# SurfacePressureSensor_V1.net
KiCad netlist of a schematic drawn in Altium Designer
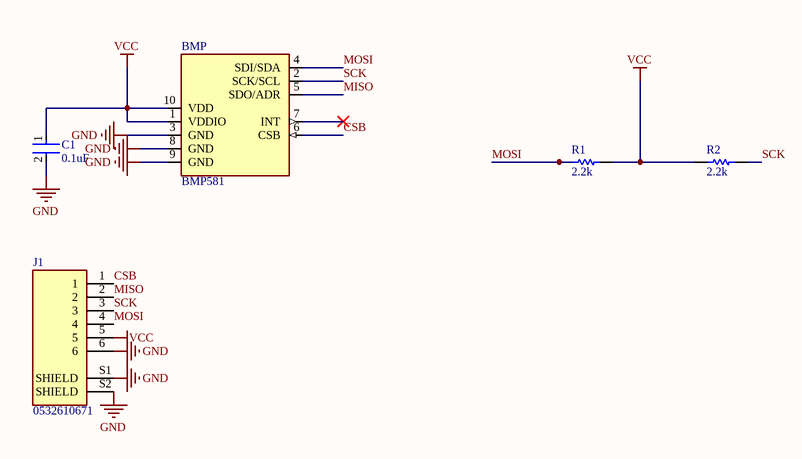
[diagram p0: SurfacePressureSensor_V1.SchDoc]

(export (version "E")
  (design (tool "Eeschema 10.0.6"))
  (components
    (comp (ref "BMP")
      (value "BMP581")
      (footprint "BMP581")
      (fields (field (name "MF") "Bosch"))
      (libsource (lib "BMP581") (part "BMP581"))
    )
    (comp (ref "C1")
      (value "0.1uF")
      (footprint "FP-C0805C-DG-MFG")
      (description "CAP CER 10UF 10V X5R 0805")
      (fields (field (name "TOLERANCE") "10%") (field (name "MANUFACTURER PART NUMBER") "C0805C106K8PACTU"))
      (libsource (lib "Altium Content Vault") (part "11868f565c42a9108669ba33697ecf6"))
    )
    (comp (ref "J1")
      (value "0532610671")
      (footprint "MOLEX_0532610671")
      (description "Picoblade Connector, 6 Circuit Single Row, Right Angle Surface Mount SMT PCB")
      (fields (field (name "DIGI-KEY_PART_NUMBER") "WM7624CT-ND") (field (name "MF") "Molex"))
      (libsource (lib "0532610671") (part "0532610671"))
    )
    (comp (ref "R1")
      (value "2.2k")
      (footprint "RESC2013X50X30LL20T20")
      (fields (field (name "MANUFACTURER") "Vishay Dale") (field (name "PART NUMBER") "CRCW08050000Z0EA"))
      (libsource (lib "Altium Content Vault") (part "RES"))
    )
    (comp (ref "R2")
      (value "2.2k")
      (footprint "RESC2013X50X30LL20T20")
      (fields (field (name "MANUFACTURER") "Vishay Dale") (field (name "PART NUMBER") "CRCW08050000Z0EA"))
      (libsource (lib "Altium Content Vault") (part "RES"))
    )
  )
  (nets
    (net (code "1") (name "/CSB") (class "Default")
      (node (ref "BMP") (pin "6") (pinfunction "CSB_6") (pintype "input"))
      (node (ref "J1") (pin "1") (pinfunction "1_1") (pintype "passive"))
    )
    (net (code "2") (name "/MISO") (class "Default")
      (node (ref "BMP") (pin "5") (pinfunction "SDO/ADR_5") (pintype "bidirectional"))
      (node (ref "J1") (pin "2") (pinfunction "2_2") (pintype "passive"))
    )
    (net (code "3") (name "/MOSI") (class "Default")
      (node (ref "BMP") (pin "4") (pinfunction "SDI/SDA_4") (pintype "bidirectional"))
      (node (ref "J1") (pin "4") (pinfunction "4_4") (pintype "passive"))
      (node (ref "R1") (pin "1") (pinfunction "1_1") (pintype "passive"))
    )
    (net (code "4") (name "/SCK") (class "Default")
      (node (ref "BMP") (pin "2") (pinfunction "SCK/SCL_2") (pintype "bidirectional"))
      (node (ref "J1") (pin "3") (pinfunction "3_3") (pintype "passive"))
      (node (ref "R2") (pin "2") (pinfunction "2_2") (pintype "passive"))
    )
    (net (code "5") (name "GND") (class "Default")
      (node (ref "BMP") (pin "3") (pinfunction "GND_3") (pintype "power_in"))
      (node (ref "BMP") (pin "8") (pinfunction "GND_8") (pintype "power_in"))
      (node (ref "BMP") (pin "9") (pinfunction "GND_9") (pintype "power_in"))
      (node (ref "C1") (pin "2") (pinfunction "2_2") (pintype "passive"))
      (node (ref "J1") (pin "6") (pinfunction "6_6") (pintype "passive"))
      (node (ref "J1") (pin "S1") (pinfunction "SHIELD_S1") (pintype "passive"))
      (node (ref "J1") (pin "S2") (pinfunction "SHIELD_S2") (pintype "passive"))
    )
    (net (code "6") (name "VCC") (class "Default")
      (node (ref "BMP") (pin "1") (pinfunction "VDDIO_1") (pintype "power_in"))
      (node (ref "BMP") (pin "10") (pinfunction "VDD_10") (pintype "power_in"))
      (node (ref "C1") (pin "1") (pinfunction "1_1") (pintype "passive"))
      (node (ref "J1") (pin "5") (pinfunction "5_5") (pintype "passive"))
      (node (ref "R1") (pin "2") (pinfunction "2_2") (pintype "passive"))
      (node (ref "R2") (pin "1") (pinfunction "1_1") (pintype "passive"))
    )
    (net (code "7") (name "unconnected-(BMP-INT-Pad7)") (class "Default")
      (node (ref "BMP") (pin "7") (pinfunction "INT_7") (pintype "output+no_connect"))
    )
  )
)
